# MotorBackplate.net
KiCad netlist of a schematic drawn in EAGLE
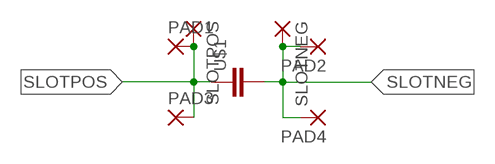
[diagram p0: schematic, sheet 1]

(export (version "E")
  (design (tool "Eeschema 10.0.6"))
  (components
    (comp (ref "PAD1")
      (value "PADNRML")
      (footprint "eagle-import:PAD_NRML")
      (libsource (lib "eagle-import") (part "PADNRML"))
    )
    (comp (ref "PAD2")
      (value "PADNRML")
      (footprint "eagle-import:PAD_NRML")
      (libsource (lib "eagle-import") (part "PADNRML"))
    )
    (comp (ref "PAD3")
      (value "PADLG")
      (footprint "eagle-import:PAD_LG")
      (libsource (lib "eagle-import") (part "PADLG"))
    )
    (comp (ref "PAD4")
      (value "PADLG")
      (footprint "eagle-import:PAD_LG")
      (libsource (lib "eagle-import") (part "PADLG"))
    )
    (comp (ref "SLOTNEG")
      (value "PAD")
      (footprint "eagle-import:SLOTPAD")
      (libsource (lib "eagle-import") (part "PAD"))
    )
    (comp (ref "SLOTPOS")
      (value "PAD")
      (footprint "eagle-import:SLOTPAD")
      (libsource (lib "eagle-import") (part "PAD"))
    )
    (comp (ref "U$1")
      (value "CAP_SMNORM")
      (footprint "eagle-import:CAP_SM")
      (libsource (lib "eagle-import") (part "CAP_SMNORM"))
    )
  )
  (nets
    (net (code "1") (name "SLOTNEG") (class "Default")
      (node (ref "PAD2") (pin "P$2") (pinfunction "P_P$2") (pintype "passive"))
      (node (ref "PAD4") (pin "P$2") (pinfunction "P_P$2") (pintype "passive"))
      (node (ref "SLOTNEG") (pin "+") (pinfunction "P_+") (pintype "passive"))
      (node (ref "U$1") (pin "2") (pinfunction "2_2") (pintype "passive"))
    )
    (net (code "2") (name "SLOTPOS") (class "Default")
      (node (ref "PAD1") (pin "P$2") (pinfunction "P_P$2") (pintype "passive"))
      (node (ref "PAD3") (pin "P$2") (pinfunction "P_P$2") (pintype "passive"))
      (node (ref "SLOTPOS") (pin "+") (pinfunction "P_+") (pintype "passive"))
      (node (ref "U$1") (pin "1") (pinfunction "1_1") (pintype "passive"))
    )
  )
)
